# power_distribution_2_21_17.net
KiCad netlist of a schematic drawn in EAGLE
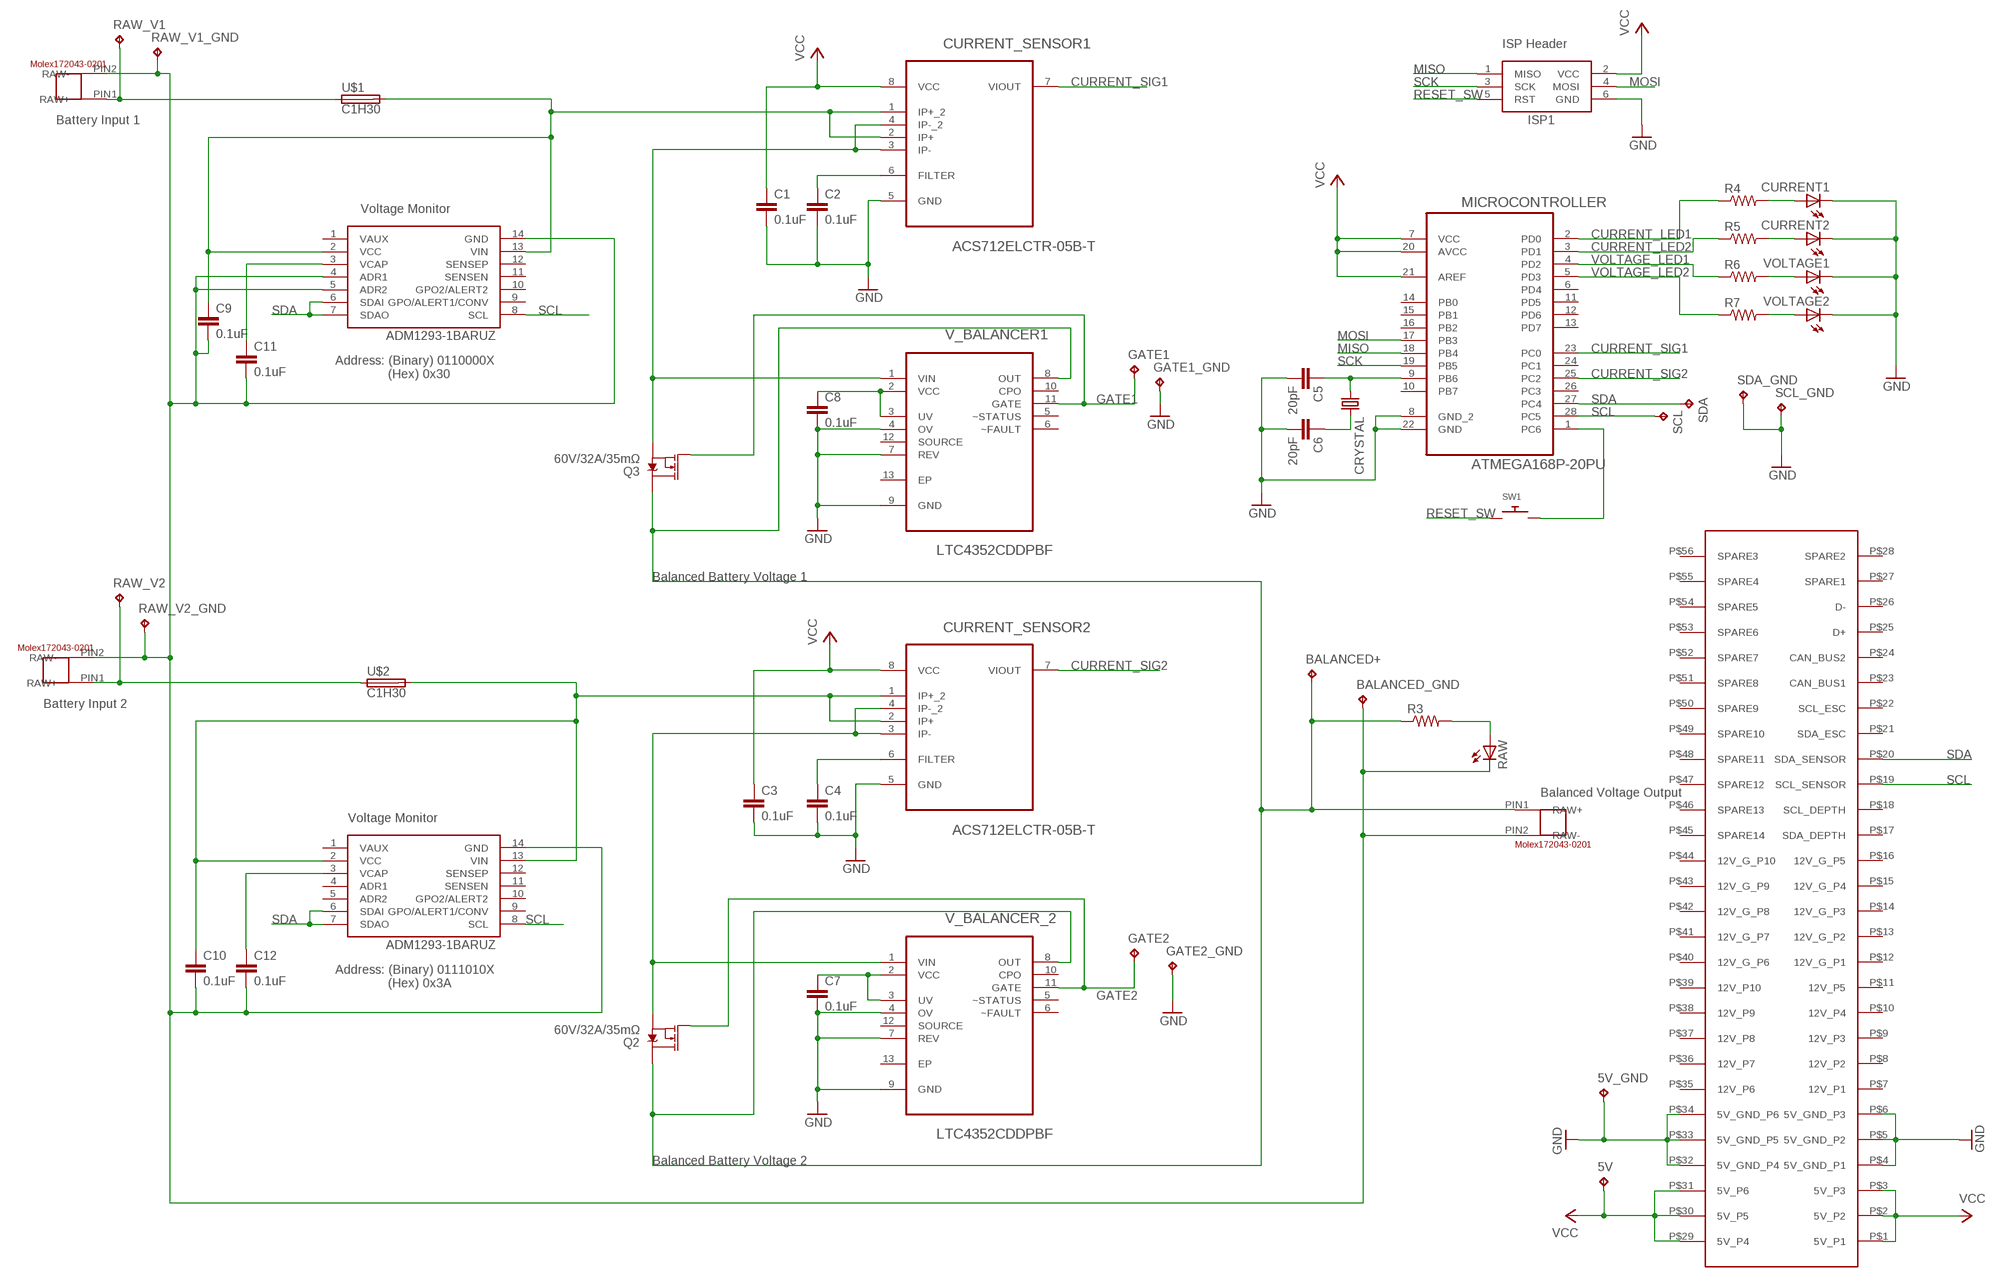
[diagram p0: schematic, sheet 1]

(export (version "E")
  (design (tool "Eeschema 10.0.6"))
  (components
    (comp (ref "5V")
      (value "TPPAD1-13")
      (footprint "eagle-import:P1-13")
      (libsource (lib "eagle-import") (part "TPPAD1-13"))
    )
    (comp (ref "5V_GND")
      (value "TPPAD1-13")
      (footprint "eagle-import:P1-13")
      (libsource (lib "eagle-import") (part "TPPAD1-13"))
    )
    (comp (ref "BALANCED+")
      (value "TPPAD1-13")
      (footprint "eagle-import:P1-13")
      (libsource (lib "eagle-import") (part "TPPAD1-13"))
    )
    (comp (ref "BALANCED_GND")
      (value "TPPAD1-13")
      (footprint "eagle-import:P1-13")
      (libsource (lib "eagle-import") (part "TPPAD1-13"))
    )
    (comp (ref "C1")
      (value "0.1uF")
      (footprint "eagle-import:CAP-PTH-SMALL-KIT")
      (libsource (lib "eagle-import") (part "0.1UF-KIT-EZ-50V-20%"))
    )
    (comp (ref "C2")
      (value "0.1uF")
      (footprint "eagle-import:CAP-PTH-SMALL-KIT")
      (libsource (lib "eagle-import") (part "0.1UF-KIT-EZ-50V-20%"))
    )
    (comp (ref "C3")
      (value "0.1uF")
      (footprint "eagle-import:CAP-PTH-SMALL-KIT")
      (libsource (lib "eagle-import") (part "0.1UF-KIT-EZ-50V-20%"))
    )
    (comp (ref "C4")
      (value "0.1uF")
      (footprint "eagle-import:CAP-PTH-SMALL-KIT")
      (libsource (lib "eagle-import") (part "0.1UF-KIT-EZ-50V-20%"))
    )
    (comp (ref "C5")
      (value "20pF")
      (footprint "eagle-import:CAP-PTH-SMALL-KIT")
      (libsource (lib "eagle-import") (part "0.1UF-KIT-EZ-50V-20%"))
    )
    (comp (ref "C6")
      (value "20pF")
      (footprint "eagle-import:CAP-PTH-SMALL-KIT")
      (libsource (lib "eagle-import") (part "0.1UF-KIT-EZ-50V-20%"))
    )
    (comp (ref "C7")
      (value "0.1uF")
      (footprint "eagle-import:CAP-PTH-SMALL-KIT")
      (libsource (lib "eagle-import") (part "0.1UF-KIT-EZ-50V-20%"))
    )
    (comp (ref "C8")
      (value "0.1uF")
      (footprint "eagle-import:CAP-PTH-SMALL-KIT")
      (libsource (lib "eagle-import") (part "0.1UF-KIT-EZ-50V-20%"))
    )
    (comp (ref "C9")
      (value "0.1uF")
      (footprint "eagle-import:CAP-PTH-SMALL-KIT")
      (libsource (lib "eagle-import") (part "0.1UF-KIT-EZ-50V-20%"))
    )
    (comp (ref "C10")
      (value "0.1uF")
      (footprint "eagle-import:CAP-PTH-SMALL-KIT")
      (libsource (lib "eagle-import") (part "0.1UF-KIT-EZ-50V-20%"))
    )
    (comp (ref "C11")
      (value "0.1uF")
      (footprint "eagle-import:CAP-PTH-SMALL-KIT")
      (libsource (lib "eagle-import") (part "0.1UF-KIT-EZ-50V-20%"))
    )
    (comp (ref "C12")
      (value "0.1uF")
      (footprint "eagle-import:CAP-PTH-SMALL-KIT")
      (libsource (lib "eagle-import") (part "0.1UF-KIT-EZ-50V-20%"))
    )
    (comp (ref "CRYSTAL")
      (value "CRYSTALHC49U-V")
      (footprint "eagle-import:HC49U-V")
      (libsource (lib "eagle-import") (part "CRYSTALHC49U-V"))
    )
    (comp (ref "CURRENT1")
      (value "LED3MM")
      (footprint "eagle-import:LED3MM")
      (libsource (lib "eagle-import") (part "LED3MM"))
    )
    (comp (ref "CURRENT2")
      (value "LED3MM")
      (footprint "eagle-import:LED3MM")
      (libsource (lib "eagle-import") (part "LED3MM"))
    )
    (comp (ref "CURRENT_SENSOR1")
      (value "ACS712ELCTR-05B-T")
      (footprint "eagle-import:SOIC127P600X175-8N")
      (libsource (lib "eagle-import") (part "ACS712ELCTR-05B-T"))
    )
    (comp (ref "CURRENT_SENSOR2")
      (value "ACS712ELCTR-05B-T")
      (footprint "eagle-import:SOIC127P600X175-8N")
      (libsource (lib "eagle-import") (part "ACS712ELCTR-05B-T"))
    )
    (comp (ref "GATE1")
      (value "TPPAD1-13")
      (footprint "eagle-import:P1-13")
      (libsource (lib "eagle-import") (part "TPPAD1-13"))
    )
    (comp (ref "GATE1_GND")
      (value "TPPAD1-13")
      (footprint "eagle-import:P1-13")
      (libsource (lib "eagle-import") (part "TPPAD1-13"))
    )
    (comp (ref "GATE2")
      (value "TPPAD1-13")
      (footprint "eagle-import:P1-13")
      (libsource (lib "eagle-import") (part "TPPAD1-13"))
    )
    (comp (ref "GATE2_GND")
      (value "TPPAD1-13")
      (footprint "eagle-import:P1-13")
      (libsource (lib "eagle-import") (part "TPPAD1-13"))
    )
    (comp (ref "INPUT1")
      (value "MOLEX172043-0201")
      (footprint "eagle-import:MOLEX172043-0201")
      (libsource (lib "eagle-import") (part "MOLEX172043-0201"))
    )
    (comp (ref "INPUT2")
      (value "MOLEX172043-0201")
      (footprint "eagle-import:MOLEX172043-0201")
      (libsource (lib "eagle-import") (part "MOLEX172043-0201"))
    )
    (comp (ref "ISP1")
      (value "AVRISP-6")
      (footprint "eagle-import:AVRISP")
      (libsource (lib "eagle-import") (part "AVRISP-6"))
    )
    (comp (ref "MICROCONTROLLER")
      (value "ATMEGA168P-20PU")
      (footprint "eagle-import:DIP254P762X457-28")
      (libsource (lib "eagle-import") (part "ATMEGA168P-20PU"))
    )
    (comp (ref "OUTPUT")
      (value "MOLEX172043-0201")
      (footprint "eagle-import:MOLEX172043-0201")
      (libsource (lib "eagle-import") (part "MOLEX172043-0201"))
    )
    (comp (ref "Q2")
      (value "60V/32A/35mΩ")
      (footprint "eagle-import:TO220V")
      (libsource (lib "eagle-import") (part "MOSFET-NCH-FQP30N06L"))
    )
    (comp (ref "Q3")
      (value "60V/32A/35mΩ")
      (footprint "eagle-import:TO220V")
      (libsource (lib "eagle-import") (part "MOSFET-NCH-FQP30N06L"))
    )
    (comp (ref "R3")
      (value "R-US_0207/12")
      (footprint "eagle-import:0207_12")
      (libsource (lib "eagle-import") (part "R-US_0207/12"))
    )
    (comp (ref "R4")
      (value "R-US_0207/12")
      (footprint "eagle-import:0207_12")
      (libsource (lib "eagle-import") (part "R-US_0207/12"))
    )
    (comp (ref "R5")
      (value "R-US_0207/12")
      (footprint "eagle-import:0207_12")
      (libsource (lib "eagle-import") (part "R-US_0207/12"))
    )
    (comp (ref "R6")
      (value "R-US_0207/12")
      (footprint "eagle-import:0207_12")
      (libsource (lib "eagle-import") (part "R-US_0207/12"))
    )
    (comp (ref "R7")
      (value "R-US_0207/12")
      (footprint "eagle-import:0207_12")
      (libsource (lib "eagle-import") (part "R-US_0207/12"))
    )
    (comp (ref "RAW")
      (value "LED3MM")
      (footprint "eagle-import:LED3MM")
      (libsource (lib "eagle-import") (part "LED3MM"))
    )
    (comp (ref "RAW_V1")
      (value "TPPAD1-13")
      (footprint "eagle-import:P1-13")
      (libsource (lib "eagle-import") (part "TPPAD1-13"))
    )
    (comp (ref "RAW_V1_GND")
      (value "TPPAD1-13")
      (footprint "eagle-import:P1-13")
      (libsource (lib "eagle-import") (part "TPPAD1-13"))
    )
    (comp (ref "RAW_V2")
      (value "TPPAD1-13")
      (footprint "eagle-import:P1-13")
      (libsource (lib "eagle-import") (part "TPPAD1-13"))
    )
    (comp (ref "RAW_V2_GND")
      (value "TPPAD1-13")
      (footprint "eagle-import:P1-13")
      (libsource (lib "eagle-import") (part "TPPAD1-13"))
    )
    (comp (ref "SCL")
      (value "TPPAD1-13")
      (footprint "eagle-import:P1-13")
      (libsource (lib "eagle-import") (part "TPPAD1-13"))
    )
    (comp (ref "SCL_GND")
      (value "TPPAD1-13")
      (footprint "eagle-import:P1-13")
      (libsource (lib "eagle-import") (part "TPPAD1-13"))
    )
    (comp (ref "SDA")
      (value "TPPAD1-13")
      (footprint "eagle-import:P1-13")
      (libsource (lib "eagle-import") (part "TPPAD1-13"))
    )
    (comp (ref "SDA_GND")
      (value "TPPAD1-13")
      (footprint "eagle-import:P1-13")
      (libsource (lib "eagle-import") (part "TPPAD1-13"))
    )
    (comp (ref "SW1")
      (value "SWITCH_PUSHBUTTONEVQ-PE")
      (footprint "eagle-import:TACT_PANA-EVQ")
      (libsource (lib "eagle-import") (part "SWITCH_PUSHBUTTONEVQ-PE"))
    )
    (comp (ref "U$1")
      (value "C1H30")
      (footprint "eagle-import:C1H30")
      (libsource (lib "eagle-import") (part "C1H30"))
    )
    (comp (ref "U$2")
      (value "C1H30")
      (footprint "eagle-import:C1H30")
      (libsource (lib "eagle-import") (part "C1H30"))
    )
    (comp (ref "U$3")
      (value "1-530844-7")
      (footprint "eagle-import:1-530844-7")
      (libsource (lib "eagle-import") (part "1-530844-7"))
    )
    (comp (ref "U$4")
      (value "ADM1293")
      (footprint "eagle-import:SOP65P640X120-14N")
      (libsource (lib "eagle-import") (part "ADM1293"))
    )
    (comp (ref "U$5")
      (value "ADM1293")
      (footprint "eagle-import:SOP65P640X120-14N")
      (libsource (lib "eagle-import") (part "ADM1293"))
    )
    (comp (ref "VOLTAGE1")
      (value "LED3MM")
      (footprint "eagle-import:LED3MM")
      (libsource (lib "eagle-import") (part "LED3MM"))
    )
    (comp (ref "VOLTAGE2")
      (value "LED3MM")
      (footprint "eagle-import:LED3MM")
      (libsource (lib "eagle-import") (part "LED3MM"))
    )
    (comp (ref "V_BALANCER1")
      (value "LTC4352CDDPBF")
      (footprint "eagle-import:DFN300X300X80-13N")
      (fields (field (name "MPN") "LTC4352CDD#PBF"))
      (libsource (lib "eagle-import") (part "LTC4352CDDPBF"))
    )
    (comp (ref "V_BALANCER_2")
      (value "LTC4352CDDPBF")
      (footprint "eagle-import:DFN300X300X80-13N")
      (fields (field (name "MPN") "LTC4352CDD#PBF"))
      (libsource (lib "eagle-import") (part "LTC4352CDDPBF"))
    )
  )
  (nets
    (net (code "1") (name "/CURRENT_LED1") (class "Default")
      (node (ref "MICROCONTROLLER") (pin "2") (pinfunction "PD0_2") (pintype "bidirectional"))
      (node (ref "R4") (pin "1") (pinfunction "1_1") (pintype "passive"))
    )
    (net (code "2") (name "/CURRENT_LED2") (class "Default")
      (node (ref "MICROCONTROLLER") (pin "3") (pinfunction "PD1_3") (pintype "bidirectional"))
      (node (ref "R5") (pin "1") (pinfunction "1_1") (pintype "passive"))
    )
    (net (code "3") (name "/CURRENT_SIG1") (class "Default")
      (node (ref "CURRENT_SENSOR1") (pin "7") (pinfunction "VIOUT_7") (pintype "output"))
      (node (ref "MICROCONTROLLER") (pin "23") (pinfunction "PC0_23") (pintype "bidirectional"))
    )
    (net (code "4") (name "/CURRENT_SIG2") (class "Default")
      (node (ref "CURRENT_SENSOR2") (pin "7") (pinfunction "VIOUT_7") (pintype "output"))
      (node (ref "MICROCONTROLLER") (pin "25") (pinfunction "PC2_25") (pintype "bidirectional"))
    )
    (net (code "5") (name "/GATE1") (class "Default")
      (node (ref "GATE1") (pin "TP") (pinfunction "TP_TP") (pintype "input"))
      (node (ref "Q3") (pin "1") (pinfunction "G_1") (pintype "bidirectional"))
      (node (ref "V_BALANCER1") (pin "11") (pinfunction "GATE_11") (pintype "output"))
    )
    (net (code "6") (name "/GATE2") (class "Default")
      (node (ref "GATE2") (pin "TP") (pinfunction "TP_TP") (pintype "input"))
      (node (ref "Q2") (pin "1") (pinfunction "G_1") (pintype "bidirectional"))
      (node (ref "V_BALANCER_2") (pin "11") (pinfunction "GATE_11") (pintype "output"))
    )
    (net (code "7") (name "/MISO") (class "Default")
      (node (ref "ISP1") (pin "1") (pinfunction "MISO_1") (pintype "input"))
      (node (ref "MICROCONTROLLER") (pin "18") (pinfunction "PB4_18") (pintype "bidirectional"))
    )
    (net (code "8") (name "/MOSI") (class "Default")
      (node (ref "ISP1") (pin "4") (pinfunction "MOSI_4") (pintype "output"))
      (node (ref "MICROCONTROLLER") (pin "17") (pinfunction "PB3_17") (pintype "bidirectional"))
    )
    (net (code "9") (name "/RESET_SW") (class "Default")
      (node (ref "ISP1") (pin "5") (pinfunction "RST_5") (pintype "output"))
      (node (ref "SW1") (pin "P$1") (pinfunction "P$1_P$1") (pintype "passive"))
    )
    (net (code "10") (name "/SCK") (class "Default")
      (node (ref "ISP1") (pin "3") (pinfunction "SCK_3") (pintype "output"))
      (node (ref "MICROCONTROLLER") (pin "19") (pinfunction "PB5_19") (pintype "bidirectional"))
    )
    (net (code "11") (name "/SCL") (class "Default")
      (node (ref "MICROCONTROLLER") (pin "28") (pinfunction "PC5_28") (pintype "bidirectional"))
      (node (ref "SCL") (pin "TP") (pinfunction "TP_TP") (pintype "input"))
      (node (ref "U$3") (pin "P$19") (pinfunction "SCL_SENSOR_P$19") (pintype "bidirectional"))
      (node (ref "U$4") (pin "8") (pinfunction "SCL_8") (pintype "bidirectional"))
      (node (ref "U$5") (pin "8") (pinfunction "SCL_8") (pintype "bidirectional"))
    )
    (net (code "12") (name "/SDA") (class "Default")
      (node (ref "MICROCONTROLLER") (pin "27") (pinfunction "PC4_27") (pintype "bidirectional"))
      (node (ref "SDA") (pin "TP") (pinfunction "TP_TP") (pintype "input"))
      (node (ref "U$3") (pin "P$20") (pinfunction "SDA_SENSOR_P$20") (pintype "bidirectional"))
      (node (ref "U$4") (pin "6") (pinfunction "SDAI_6") (pintype "bidirectional"))
      (node (ref "U$4") (pin "7") (pinfunction "SDAO_7") (pintype "bidirectional"))
      (node (ref "U$5") (pin "6") (pinfunction "SDAI_6") (pintype "bidirectional"))
      (node (ref "U$5") (pin "7") (pinfunction "SDAO_7") (pintype "bidirectional"))
    )
    (net (code "13") (name "/VOLTAGE_LED1") (class "Default")
      (node (ref "MICROCONTROLLER") (pin "4") (pinfunction "PD2_4") (pintype "bidirectional"))
      (node (ref "R6") (pin "1") (pinfunction "1_1") (pintype "passive"))
    )
    (net (code "14") (name "/VOLTAGE_LED2") (class "Default")
      (node (ref "MICROCONTROLLER") (pin "5") (pinfunction "PD3_5") (pintype "bidirectional"))
      (node (ref "R7") (pin "1") (pinfunction "1_1") (pintype "passive"))
    )
    (net (code "15") (name "GND") (class "Default")
      (node (ref "5V_GND") (pin "TP") (pinfunction "TP_TP") (pintype "input"))
      (node (ref "C1") (pin "2") (pinfunction "2_2") (pintype "passive"))
      (node (ref "C2") (pin "2") (pinfunction "2_2") (pintype "passive"))
      (node (ref "C3") (pin "2") (pinfunction "2_2") (pintype "passive"))
      (node (ref "C4") (pin "2") (pinfunction "2_2") (pintype "passive"))
      (node (ref "C5") (pin "2") (pinfunction "2_2") (pintype "passive"))
      (node (ref "C6") (pin "2") (pinfunction "2_2") (pintype "passive"))
      (node (ref "C7") (pin "2") (pinfunction "2_2") (pintype "passive"))
      (node (ref "C8") (pin "2") (pinfunction "2_2") (pintype "passive"))
      (node (ref "CURRENT1") (pin "K") (pinfunction "C_K") (pintype "passive"))
      (node (ref "CURRENT2") (pin "K") (pinfunction "C_K") (pintype "passive"))
      (node (ref "CURRENT_SENSOR1") (pin "5") (pinfunction "GND_5") (pintype "passive"))
      (node (ref "CURRENT_SENSOR2") (pin "5") (pinfunction "GND_5") (pintype "passive"))
      (node (ref "GATE1_GND") (pin "TP") (pinfunction "TP_TP") (pintype "input"))
      (node (ref "GATE2_GND") (pin "TP") (pinfunction "TP_TP") (pintype "input"))
      (node (ref "ISP1") (pin "6") (pinfunction "GND_6") (pintype "power_in"))
      (node (ref "MICROCONTROLLER") (pin "22") (pinfunction "GND_22") (pintype "passive"))
      (node (ref "MICROCONTROLLER") (pin "8") (pinfunction "GND_2_8") (pintype "passive"))
      (node (ref "SCL_GND") (pin "TP") (pinfunction "TP_TP") (pintype "input"))
      (node (ref "SDA_GND") (pin "TP") (pinfunction "TP_TP") (pintype "input"))
      (node (ref "U$3") (pin "P$32") (pinfunction "5V_GND_P4_P$32") (pintype "bidirectional"))
      (node (ref "U$3") (pin "P$33") (pinfunction "5V_GND_P5_P$33") (pintype "bidirectional"))
      (node (ref "U$3") (pin "P$34") (pinfunction "5V_GND_P6_P$34") (pintype "bidirectional"))
      (node (ref "U$3") (pin "P$4") (pinfunction "5V_GND_P1_P$4") (pintype "bidirectional"))
      (node (ref "U$3") (pin "P$5") (pinfunction "5V_GND_P2_P$5") (pintype "bidirectional"))
      (node (ref "U$3") (pin "P$6") (pinfunction "5V_GND_P3_P$6") (pintype "bidirectional"))
      (node (ref "VOLTAGE1") (pin "K") (pinfunction "C_K") (pintype "passive"))
      (node (ref "VOLTAGE2") (pin "K") (pinfunction "C_K") (pintype "passive"))
      (node (ref "V_BALANCER1") (pin "4") (pinfunction "OV_4") (pintype "input"))
      (node (ref "V_BALANCER1") (pin "7") (pinfunction "REV_7") (pintype "input"))
      (node (ref "V_BALANCER1") (pin "9") (pinfunction "GND_9") (pintype "passive"))
      (node (ref "V_BALANCER_2") (pin "4") (pinfunction "OV_4") (pintype "input"))
      (node (ref "V_BALANCER_2") (pin "7") (pinfunction "REV_7") (pintype "input"))
      (node (ref "V_BALANCER_2") (pin "9") (pinfunction "GND_9") (pintype "passive"))
    )
    (net (code "16") (name "Net-(C6-Pad1)") (class "Default")
      (node (ref "C6") (pin "1") (pinfunction "1_1") (pintype "passive"))
      (node (ref "CRYSTAL") (pin "2") (pinfunction "2_2") (pintype "passive"))
    )
    (net (code "17") (name "Net-(CURRENT1-PadA)") (class "Default")
      (node (ref "CURRENT1") (pin "A") (pinfunction "A_A") (pintype "passive"))
      (node (ref "R4") (pin "2") (pinfunction "2_2") (pintype "passive"))
    )
    (net (code "18") (name "Net-(CURRENT2-PadA)") (class "Default")
      (node (ref "CURRENT2") (pin "A") (pinfunction "A_A") (pintype "passive"))
      (node (ref "R5") (pin "2") (pinfunction "2_2") (pintype "passive"))
    )
    (net (code "19") (name "Net-(CURRENT_SENSOR1-FILTER)") (class "Default")
      (node (ref "C2") (pin "1") (pinfunction "1_1") (pintype "passive"))
      (node (ref "CURRENT_SENSOR1") (pin "6") (pinfunction "FILTER_6") (pintype "input"))
    )
    (net (code "20") (name "Net-(CURRENT_SENSOR1-IP+)") (class "Default")
      (node (ref "C9") (pin "1") (pinfunction "1_1") (pintype "passive"))
      (node (ref "CURRENT_SENSOR1") (pin "1") (pinfunction "IP+_2_1") (pintype "input"))
      (node (ref "CURRENT_SENSOR1") (pin "2") (pinfunction "IP+_2") (pintype "input"))
      (node (ref "U$1") (pin "P$2") (pinfunction "2_P$2") (pintype "passive"))
      (node (ref "U$4") (pin "13") (pinfunction "VIN_13") (pintype "bidirectional"))
      (node (ref "U$4") (pin "2") (pinfunction "VCC_2") (pintype "bidirectional"))
    )
    (net (code "21") (name "Net-(CURRENT_SENSOR1-IP-)") (class "Default")
      (node (ref "CURRENT_SENSOR1") (pin "3") (pinfunction "IP-_3") (pintype "input"))
      (node (ref "CURRENT_SENSOR1") (pin "4") (pinfunction "IP-_2_4") (pintype "input"))
      (node (ref "Q3") (pin "3") (pinfunction "S_3") (pintype "bidirectional"))
      (node (ref "V_BALANCER1") (pin "1") (pinfunction "VIN_1") (pintype "power_in"))
    )
    (net (code "22") (name "Net-(CURRENT_SENSOR2-FILTER)") (class "Default")
      (node (ref "C4") (pin "1") (pinfunction "1_1") (pintype "passive"))
      (node (ref "CURRENT_SENSOR2") (pin "6") (pinfunction "FILTER_6") (pintype "input"))
    )
    (net (code "23") (name "Net-(CURRENT_SENSOR2-IP+)") (class "Default")
      (node (ref "C10") (pin "1") (pinfunction "1_1") (pintype "passive"))
      (node (ref "CURRENT_SENSOR2") (pin "1") (pinfunction "IP+_2_1") (pintype "input"))
      (node (ref "CURRENT_SENSOR2") (pin "2") (pinfunction "IP+_2") (pintype "input"))
      (node (ref "U$2") (pin "P$2") (pinfunction "2_P$2") (pintype "passive"))
      (node (ref "U$5") (pin "13") (pinfunction "VIN_13") (pintype "bidirectional"))
      (node (ref "U$5") (pin "2") (pinfunction "VCC_2") (pintype "bidirectional"))
    )
    (net (code "24") (name "Net-(CURRENT_SENSOR2-IP-)") (class "Default")
      (node (ref "CURRENT_SENSOR2") (pin "3") (pinfunction "IP-_3") (pintype "input"))
      (node (ref "CURRENT_SENSOR2") (pin "4") (pinfunction "IP-_2_4") (pintype "input"))
      (node (ref "Q2") (pin "3") (pinfunction "S_3") (pintype "bidirectional"))
      (node (ref "V_BALANCER_2") (pin "1") (pinfunction "VIN_1") (pintype "power_in"))
    )
    (net (code "25") (name "Net-(INPUT1-RAW+)") (class "Default")
      (node (ref "INPUT1") (pin "PIN1") (pinfunction "RAW+_PIN1") (pintype "bidirectional"))
      (node (ref "RAW_V1") (pin "TP") (pinfunction "TP_TP") (pintype "input"))
      (node (ref "U$1") (pin "P$1") (pinfunction "1_P$1") (pintype "passive"))
    )
    (net (code "26") (name "Net-(INPUT1-RAW-)") (class "Default")
      (node (ref "BALANCED_GND") (pin "TP") (pinfunction "TP_TP") (pintype "input"))
      (node (ref "C10") (pin "2") (pinfunction "2_2") (pintype "passive"))
      (node (ref "C11") (pin "2") (pinfunction "2_2") (pintype "passive"))
      (node (ref "C12") (pin "2") (pinfunction "2_2") (pintype "passive"))
      (node (ref "C9") (pin "2") (pinfunction "2_2") (pintype "passive"))
      (node (ref "INPUT1") (pin "PIN2") (pinfunction "RAW-_PIN2") (pintype "bidirectional"))
      (node (ref "INPUT2") (pin "PIN2") (pinfunction "RAW-_PIN2") (pintype "bidirectional"))
      (node (ref "OUTPUT") (pin "PIN2") (pinfunction "RAW-_PIN2") (pintype "bidirectional"))
      (node (ref "RAW") (pin "K") (pinfunction "C_K") (pintype "passive"))
      (node (ref "RAW_V1_GND") (pin "TP") (pinfunction "TP_TP") (pintype "input"))
      (node (ref "RAW_V2_GND") (pin "TP") (pinfunction "TP_TP") (pintype "input"))
      (node (ref "U$4") (pin "14") (pinfunction "GND_14") (pintype "bidirectional"))
      (node (ref "U$4") (pin "4") (pinfunction "ADR1_4") (pintype "bidirectional"))
      (node (ref "U$4") (pin "5") (pinfunction "ADR2_5") (pintype "bidirectional"))
      (node (ref "U$5") (pin "14") (pinfunction "GND_14") (pintype "bidirectional"))
    )
    (net (code "27") (name "Net-(INPUT2-RAW+)") (class "Default")
      (node (ref "INPUT2") (pin "PIN1") (pinfunction "RAW+_PIN1") (pintype "bidirectional"))
      (node (ref "RAW_V2") (pin "TP") (pinfunction "TP_TP") (pintype "input"))
      (node (ref "U$2") (pin "P$1") (pinfunction "1_P$1") (pintype "passive"))
    )
    (net (code "28") (name "Net-(MICROCONTROLLER-PB6)") (class "Default")
      (node (ref "C5") (pin "1") (pinfunction "1_1") (pintype "passive"))
      (node (ref "CRYSTAL") (pin "1") (pinfunction "1_1") (pintype "passive"))
      (node (ref "MICROCONTROLLER") (pin "9") (pinfunction "PB6_9") (pintype "bidirectional"))
    )
    (net (code "29") (name "Net-(MICROCONTROLLER-PC6)") (class "Default")
      (node (ref "MICROCONTROLLER") (pin "1") (pinfunction "PC6_1") (pintype "bidirectional"))
      (node (ref "SW1") (pin "P$2") (pinfunction "P$2_P$2") (pintype "passive"))
    )
    (net (code "30") (name "Net-(OUTPUT-RAW+)") (class "Default")
      (node (ref "BALANCED+") (pin "TP") (pinfunction "TP_TP") (pintype "input"))
      (node (ref "OUTPUT") (pin "PIN1") (pinfunction "RAW+_PIN1") (pintype "bidirectional"))
      (node (ref "Q2") (pin "2") (pinfunction "D_2") (pintype "bidirectional"))
      (node (ref "Q3") (pin "2") (pinfunction "D_2") (pintype "bidirectional"))
      (node (ref "R3") (pin "1") (pinfunction "1_1") (pintype "passive"))
      (node (ref "V_BALANCER1") (pin "8") (pinfunction "OUT_8") (pintype "output"))
      (node (ref "V_BALANCER_2") (pin "8") (pinfunction "OUT_8") (pintype "output"))
    )
    (net (code "31") (name "Net-(R3-Pad2)") (class "Default")
      (node (ref "R3") (pin "2") (pinfunction "2_2") (pintype "passive"))
      (node (ref "RAW") (pin "A") (pinfunction "A_A") (pintype "passive"))
    )
    (net (code "32") (name "Net-(R6-Pad2)") (class "Default")
      (node (ref "R6") (pin "2") (pinfunction "2_2") (pintype "passive"))
      (node (ref "VOLTAGE1") (pin "A") (pinfunction "A_A") (pintype "passive"))
    )
    (net (code "33") (name "Net-(R7-Pad2)") (class "Default")
      (node (ref "R7") (pin "2") (pinfunction "2_2") (pintype "passive"))
      (node (ref "VOLTAGE2") (pin "A") (pinfunction "A_A") (pintype "passive"))
    )
    (net (code "34") (name "Net-(U$4-VCAP)") (class "Default")
      (node (ref "C11") (pin "1") (pinfunction "1_1") (pintype "passive"))
      (node (ref "U$4") (pin "3") (pinfunction "VCAP_3") (pintype "bidirectional"))
    )
    (net (code "35") (name "Net-(U$5-VCAP)") (class "Default")
      (node (ref "C12") (pin "1") (pinfunction "1_1") (pintype "passive"))
      (node (ref "U$5") (pin "3") (pinfunction "VCAP_3") (pintype "bidirectional"))
    )
    (net (code "36") (name "Net-(V_BALANCER1-UV)") (class "Default")
      (node (ref "C8") (pin "1") (pinfunction "1_1") (pintype "passive"))
      (node (ref "V_BALANCER1") (pin "2") (pinfunction "VCC_2") (pintype "power_in"))
      (node (ref "V_BALANCER1") (pin "3") (pinfunction "UV_3") (pintype "input"))
    )
    (net (code "37") (name "Net-(V_BALANCER_2-UV)") (class "Default")
      (node (ref "C7") (pin "1") (pinfunction "1_1") (pintype "passive"))
      (node (ref "V_BALANCER_2") (pin "2") (pinfunction "VCC_2") (pintype "power_in"))
      (node (ref "V_BALANCER_2") (pin "3") (pinfunction "UV_3") (pintype "input"))
    )
    (net (code "38") (name "VCC") (class "Default")
      (node (ref "5V") (pin "TP") (pinfunction "TP_TP") (pintype "input"))
      (node (ref "C1") (pin "1") (pinfunction "1_1") (pintype "passive"))
      (node (ref "C3") (pin "1") (pinfunction "1_1") (pintype "passive"))
      (node (ref "CURRENT_SENSOR1") (pin "8") (pinfunction "VCC_8") (pintype "power_in"))
      (node (ref "CURRENT_SENSOR2") (pin "8") (pinfunction "VCC_8") (pintype "power_in"))
      (node (ref "ISP1") (pin "2") (pinfunction "VCC_2") (pintype "power_in"))
      (node (ref "MICROCONTROLLER") (pin "20") (pinfunction "AVCC_20") (pintype "power_in"))
      (node (ref "MICROCONTROLLER") (pin "21") (pinfunction "AREF_21") (pintype "input"))
      (node (ref "MICROCONTROLLER") (pin "7") (pinfunction "VCC_7") (pintype "power_in"))
      (node (ref "U$3") (pin "P$1") (pinfunction "5V_P1_P$1") (pintype "bidirectional"))
      (node (ref "U$3") (pin "P$2") (pinfunction "5V_P2_P$2") (pintype "bidirectional"))
      (node (ref "U$3") (pin "P$29") (pinfunction "5V_P4_P$29") (pintype "bidirectional"))
      (node (ref "U$3") (pin "P$3") (pinfunction "5V_P3_P$3") (pintype "bidirectional"))
      (node (ref "U$3") (pin "P$30") (pinfunction "5V_P5_P$30") (pintype "bidirectional"))
      (node (ref "U$3") (pin "P$31") (pinfunction "5V_P6_P$31") (pintype "bidirectional"))
    )
    (net (code "39") (name "unconnected-(MICROCONTROLLER-PB0-Pad14)") (class "Default")
      (node (ref "MICROCONTROLLER") (pin "14") (pinfunction "PB0_14") (pintype "bidirectional"))
    )
    (net (code "40") (name "unconnected-(MICROCONTROLLER-PB1-Pad15)") (class "Default")
      (node (ref "MICROCONTROLLER") (pin "15") (pinfunction "PB1_15") (pintype "bidirectional"))
    )
    (net (code "41") (name "unconnected-(MICROCONTROLLER-PB2-Pad16)") (class "Default")
      (node (ref "MICROCONTROLLER") (pin "16") (pinfunction "PB2_16") (pintype "bidirectional"))
    )
    (net (code "42") (name "unconnected-(MICROCONTROLLER-PB7-Pad10)") (class "Default")
      (node (ref "MICROCONTROLLER") (pin "10") (pinfunction "PB7_10") (pintype "bidirectional"))
    )
    (net (code "43") (name "unconnected-(MICROCONTROLLER-PC1-Pad24)") (class "Default")
      (node (ref "MICROCONTROLLER") (pin "24") (pinfunction "PC1_24") (pintype "bidirectional"))
    )
    (net (code "44") (name "unconnected-(MICROCONTROLLER-PC3-Pad26)") (class "Default")
      (node (ref "MICROCONTROLLER") (pin "26") (pinfunction "PC3_26") (pintype "bidirectional"))
    )
    (net (code "45") (name "unconnected-(MICROCONTROLLER-PD4-Pad6)") (class "Default")
      (node (ref "MICROCONTROLLER") (pin "6") (pinfunction "PD4_6") (pintype "bidirectional"))
    )
    (net (code "46") (name "unconnected-(MICROCONTROLLER-PD5-Pad11)") (class "Default")
      (node (ref "MICROCONTROLLER") (pin "11") (pinfunction "PD5_11") (pintype "bidirectional"))
    )
    (net (code "47") (name "unconnected-(MICROCONTROLLER-PD6-Pad12)") (class "Default")
      (node (ref "MICROCONTROLLER") (pin "12") (pinfunction "PD6_12") (pintype "bidirectional"))
    )
    (net (code "48") (name "unconnected-(MICROCONTROLLER-PD7-Pad13)") (class "Default")
      (node (ref "MICROCONTROLLER") (pin "13") (pinfunction "PD7_13") (pintype "bidirectional"))
    )
    (net (code "49") (name "unconnected-(U$3-12V_G_P1-PadP$12)") (class "Default")
      (node (ref "U$3") (pin "P$12") (pinfunction "12V_G_P1_P$12") (pintype "bidirectional"))
    )
    (net (code "50") (name "unconnected-(U$3-12V_G_P2-PadP$13)") (class "Default")
      (node (ref "U$3") (pin "P$13") (pinfunction "12V_G_P2_P$13") (pintype "bidirectional"))
    )
    (net (code "51") (name "unconnected-(U$3-12V_G_P3-PadP$14)") (class "Default")
      (node (ref "U$3") (pin "P$14") (pinfunction "12V_G_P3_P$14") (pintype "bidirectional"))
    )
    (net (code "52") (name "unconnected-(U$3-12V_G_P4-PadP$15)") (class "Default")
      (node (ref "U$3") (pin "P$15") (pinfunction "12V_G_P4_P$15") (pintype "bidirectional"))
    )
    (net (code "53") (name "unconnected-(U$3-12V_G_P5-PadP$16)") (class "Default")
      (node (ref "U$3") (pin "P$16") (pinfunction "12V_G_P5_P$16") (pintype "bidirectional"))
    )
    (net (code "54") (name "unconnected-(U$3-12V_G_P6-PadP$40)") (class "Default")
      (node (ref "U$3") (pin "P$40") (pinfunction "12V_G_P6_P$40") (pintype "bidirectional"))
    )
    (net (code "55") (name "unconnected-(U$3-12V_G_P7-PadP$41)") (class "Default")
      (node (ref "U$3") (pin "P$41") (pinfunction "12V_G_P7_P$41") (pintype "bidirectional"))
    )
    (net (code "56") (name "unconnected-(U$3-12V_G_P8-PadP$42)") (class "Default")
      (node (ref "U$3") (pin "P$42") (pinfunction "12V_G_P8_P$42") (pintype "bidirectional"))
    )
    (net (code "57") (name "unconnected-(U$3-12V_G_P9-PadP$43)") (class "Default")
      (node (ref "U$3") (pin "P$43") (pinfunction "12V_G_P9_P$43") (pintype "bidirectional"))
    )
    (net (code "58") (name "unconnected-(U$3-12V_G_P10-PadP$44)") (class "Default")
      (node (ref "U$3") (pin "P$44") (pinfunction "12V_G_P10_P$44") (pintype "bidirectional"))
    )
    (net (code "59") (name "unconnected-(U$3-12V_P1-PadP$7)") (class "Default")
      (node (ref "U$3") (pin "P$7") (pinfunction "12V_P1_P$7") (pintype "bidirectional"))
    )
    (net (code "60") (name "unconnected-(U$3-12V_P2-PadP$8)") (class "Default")
      (node (ref "U$3") (pin "P$8") (pinfunction "12V_P2_P$8") (pintype "bidirectional"))
    )
    (net (code "61") (name "unconnected-(U$3-12V_P3-PadP$9)") (class "Default")
      (node (ref "U$3") (pin "P$9") (pinfunction "12V_P3_P$9") (pintype "bidirectional"))
    )
    (net (code "62") (name "unconnected-(U$3-12V_P4-PadP$10)") (class "Default")
      (node (ref "U$3") (pin "P$10") (pinfunction "12V_P4_P$10") (pintype "bidirectional"))
    )
    (net (code "63") (name "unconnected-(U$3-12V_P5-PadP$11)") (class "Default")
      (node (ref "U$3") (pin "P$11") (pinfunction "12V_P5_P$11") (pintype "bidirectional"))
    )
    (net (code "64") (name "unconnected-(U$3-12V_P6-PadP$35)") (class "Default")
      (node (ref "U$3") (pin "P$35") (pinfunction "12V_P6_P$35") (pintype "bidirectional"))
    )
    (net (code "65") (name "unconnected-(U$3-12V_P7-PadP$36)") (class "Default")
      (node (ref "U$3") (pin "P$36") (pinfunction "12V_P7_P$36") (pintype "bidirectional"))
    )
    (net (code "66") (name "unconnected-(U$3-12V_P8-PadP$37)") (class "Default")
      (node (ref "U$3") (pin "P$37") (pinfunction "12V_P8_P$37") (pintype "bidirectional"))
    )
    (net (code "67") (name "unconnected-(U$3-12V_P9-PadP$38)") (class "Default")
      (node (ref "U$3") (pin "P$38") (pinfunction "12V_P9_P$38") (pintype "bidirectional"))
    )
    (net (code "68") (name "unconnected-(U$3-12V_P10-PadP$39)") (class "Default")
      (node (ref "U$3") (pin "P$39") (pinfunction "12V_P10_P$39") (pintype "bidirectional"))
    )
    (net (code "69") (name "unconnected-(U$3-CAN_BUS1-PadP$23)") (class "Default")
      (node (ref "U$3") (pin "P$23") (pinfunction "CAN_BUS1_P$23") (pintype "bidirectional"))
    )
    (net (code "70") (name "unconnected-(U$3-CAN_BUS2-PadP$24)") (class "Default")
      (node (ref "U$3") (pin "P$24") (pinfunction "CAN_BUS2_P$24") (pintype "bidirectional"))
    )
    (net (code "71") (name "unconnected-(U$3-D+-PadP$25)") (class "Default")
      (node (ref "U$3") (pin "P$25") (pinfunction "D+_P$25") (pintype "bidirectional"))
    )
    (net (code "72") (name "unconnected-(U$3-D--PadP$26)") (class "Default")
      (node (ref "U$3") (pin "P$26") (pinfunction "D-_P$26") (pintype "bidirectional"))
    )
    (net (code "73") (name "unconnected-(U$3-SCL_DEPTH-PadP$18)") (class "Default")
      (node (ref "U$3") (pin "P$18") (pinfunction "SCL_DEPTH_P$18") (pintype "bidirectional"))
    )
    (net (code "74") (name "unconnected-(U$3-SCL_ESC-PadP$22)") (class "Default")
      (node (ref "U$3") (pin "P$22") (pinfunction "SCL_ESC_P$22") (pintype "bidirectional"))
    )
    (net (code "75") (name "unconnected-(U$3-SDA_DEPTH-PadP$17)") (class "Default")
      (node (ref "U$3") (pin "P$17") (pinfunction "SDA_DEPTH_P$17") (pintype "bidirectional"))
    )
    (net (code "76") (name "unconnected-(U$3-SDA_ESC-PadP$21)") (class "Default")
      (node (ref "U$3") (pin "P$21") (pinfunction "SDA_ESC_P$21") (pintype "bidirectional"))
    )
    (net (code "77") (name "unconnected-(U$3-SPARE1-PadP$27)") (class "Default")
      (node (ref "U$3") (pin "P$27") (pinfunction "SPARE1_P$27") (pintype "bidirectional"))
    )
    (net (code "78") (name "unconnected-(U$3-SPARE2-PadP$28)") (class "Default")
      (node (ref "U$3") (pin "P$28") (pinfunction "SPARE2_P$28") (pintype "bidirectional"))
    )
    (net (code "79") (name "unconnected-(U$3-SPARE3-PadP$56)") (class "Default")
      (node (ref "U$3") (pin "P$56") (pinfunction "SPARE3_P$56") (pintype "bidirectional"))
    )
    (net (code "80") (name "unconnected-(U$3-SPARE4-PadP$55)") (class "Default")
      (node (ref "U$3") (pin "P$55") (pinfunction "SPARE4_P$55") (pintype "bidirectional"))
    )
    (net (code "81") (name "unconnected-(U$3-SPARE5-PadP$54)") (class "Default")
      (node (ref "U$3") (pin "P$54") (pinfunction "SPARE5_P$54") (pintype "bidirectional"))
    )
    (net (code "82") (name "unconnected-(U$3-SPARE6-PadP$53)") (class "Default")
      (node (ref "U$3") (pin "P$53") (pinfunction "SPARE6_P$53") (pintype "bidirectional"))
    )
    (net (code "83") (name "unconnected-(U$3-SPARE7-PadP$52)") (class "Default")
      (node (ref "U$3") (pin "P$52") (pinfunction "SPARE7_P$52") (pintype "bidirectional"))
    )
    (net (code "84") (name "unconnected-(U$3-SPARE8-PadP$51)") (class "Default")
      (node (ref "U$3") (pin "P$51") (pinfunction "SPARE8_P$51") (pintype "bidirectional"))
    )
    (net (code "85") (name "unconnected-(U$3-SPARE9-PadP$50)") (class "Default")
      (node (ref "U$3") (pin "P$50") (pinfunction "SPARE9_P$50") (pintype "bidirectional"))
    )
    (net (code "86") (name "unconnected-(U$3-SPARE10-PadP$49)") (class "Default")
      (node (ref "U$3") (pin "P$49") (pinfunction "SPARE10_P$49") (pintype "bidirectional"))
    )
    (net (code "87") (name "unconnected-(U$3-SPARE11-PadP$48)") (class "Default")
      (node (ref "U$3") (pin "P$48") (pinfunction "SPARE11_P$48") (pintype "bidirectional"))
    )
    (net (code "88") (name "unconnected-(U$3-SPARE12-PadP$47)") (class "Default")
      (node (ref "U$3") (pin "P$47") (pinfunction "SPARE12_P$47") (pintype "bidirectional"))
    )
    (net (code "89") (name "unconnected-(U$3-SPARE13-PadP$46)") (class "Default")
      (node (ref "U$3") (pin "P$46") (pinfunction "SPARE13_P$46") (pintype "bidirectional"))
    )
    (net (code "90") (name "unconnected-(U$3-SPARE14-PadP$45)") (class "Default")
      (node (ref "U$3") (pin "P$45") (pinfunction "SPARE14_P$45") (pintype "bidirectional"))
    )
    (net (code "91") (name "unconnected-(U$4-GPO2{slash}ALERT2-Pad10)") (class "Default")
      (node (ref "U$4") (pin "10") (pinfunction "GPO2/ALERT2_10") (pintype "bidirectional"))
    )
    (net (code "92") (name "unconnected-(U$4-GPO{slash}ALERT1{slash}CONV-Pad9)") (class "Default")
      (node (ref "U$4") (pin "9") (pinfunction "GPO/ALERT1/CONV_9") (pintype "bidirectional"))
    )
    (net (code "93") (name "unconnected-(U$4-SENSEN-Pad11)") (class "Default")
      (node (ref "U$4") (pin "11") (pinfunction "SENSEN_11") (pintype "bidirectional"))
    )
    (net (code "94") (name "unconnected-(U$4-SENSEP-Pad12)") (class "Default")
      (node (ref "U$4") (pin "12") (pinfunction "SENSEP_12") (pintype "bidirectional"))
    )
    (net (code "95") (name "unconnected-(U$4-VAUX-Pad1)") (class "Default")
      (node (ref "U$4") (pin "1") (pinfunction "VAUX_1") (pintype "bidirectional"))
    )
    (net (code "96") (name "unconnected-(U$5-ADR1-Pad4)") (class "Default")
      (node (ref "U$5") (pin "4") (pinfunction "ADR1_4") (pintype "bidirectional"))
    )
    (net (code "97") (name "unconnected-(U$5-ADR2-Pad5)") (class "Default")
      (node (ref "U$5") (pin "5") (pinfunction "ADR2_5") (pintype "bidirectional"))
    )
    (net (code "98") (name "unconnected-(U$5-GPO2{slash}ALERT2-Pad10)") (class "Default")
      (node (ref "U$5") (pin "10") (pinfunction "GPO2/ALERT2_10") (pintype "bidirectional"))
    )
    (net (code "99") (name "unconnected-(U$5-GPO{slash}ALERT1{slash}CONV-Pad9)") (class "Default")
      (node (ref "U$5") (pin "9") (pinfunction "GPO/ALERT1/CONV_9") (pintype "bidirectional"))
    )
    (net (code "100") (name "unconnected-(U$5-SENSEN-Pad11)") (class "Default")
      (node (ref "U$5") (pin "11") (pinfunction "SENSEN_11") (pintype "bidirectional"))
    )
    (net (code "101") (name "unconnected-(U$5-SENSEP-Pad12)") (class "Default")
      (node (ref "U$5") (pin "12") (pinfunction "SENSEP_12") (pintype "bidirectional"))
    )
    (net (code "102") (name "unconnected-(U$5-VAUX-Pad1)") (class "Default")
      (node (ref "U$5") (pin "1") (pinfunction "VAUX_1") (pintype "bidirectional"))
    )
    (net (code "103") (name "unconnected-(V_BALANCER1-CPO-Pad10)") (class "Default")
      (node (ref "V_BALANCER1") (pin "10") (pinfunction "CPO_10") (pintype "output"))
    )
    (net (code "104") (name "unconnected-(V_BALANCER1-EP-Pad13)") (class "Default")
      (node (ref "V_BALANCER1") (pin "13") (pinfunction "EP_13") (pintype "passive"))
    )
    (net (code "105") (name "unconnected-(V_BALANCER1-SOURCE-Pad12)") (class "Default")
      (node (ref "V_BALANCER1") (pin "12") (pinfunction "SOURCE_12") (pintype "input"))
    )
    (net (code "106") (name "unconnected-(V_BALANCER1-~{FAULT}-Pad6)") (class "Default")
      (node (ref "V_BALANCER1") (pin "6") (pinfunction "~{FAULT}_6") (pintype "output"))
    )
    (net (code "107") (name "unconnected-(V_BALANCER1-~{STATUS}-Pad5)") (class "Default")
      (node (ref "V_BALANCER1") (pin "5") (pinfunction "~{STATUS}_5") (pintype "output"))
    )
    (net (code "108") (name "unconnected-(V_BALANCER_2-CPO-Pad10)") (class "Default")
      (node (ref "V_BALANCER_2") (pin "10") (pinfunction "CPO_10") (pintype "output"))
    )
    (net (code "109") (name "unconnected-(V_BALANCER_2-EP-Pad13)") (class "Default")
      (node (ref "V_BALANCER_2") (pin "13") (pinfunction "EP_13") (pintype "passive"))
    )
    (net (code "110") (name "unconnected-(V_BALANCER_2-SOURCE-Pad12)") (class "Default")
      (node (ref "V_BALANCER_2") (pin "12") (pinfunction "SOURCE_12") (pintype "input"))
    )
    (net (code "111") (name "unconnected-(V_BALANCER_2-~{FAULT}-Pad6)") (class "Default")
      (node (ref "V_BALANCER_2") (pin "6") (pinfunction "~{FAULT}_6") (pintype "output"))
    )
    (net (code "112") (name "unconnected-(V_BALANCER_2-~{STATUS}-Pad5)") (class "Default")
      (node (ref "V_BALANCER_2") (pin "5") (pinfunction "~{STATUS}_5") (pintype "output"))
    )
  )
)
